# ASM4001.net
KiCad netlist of a schematic drawn in EAGLE
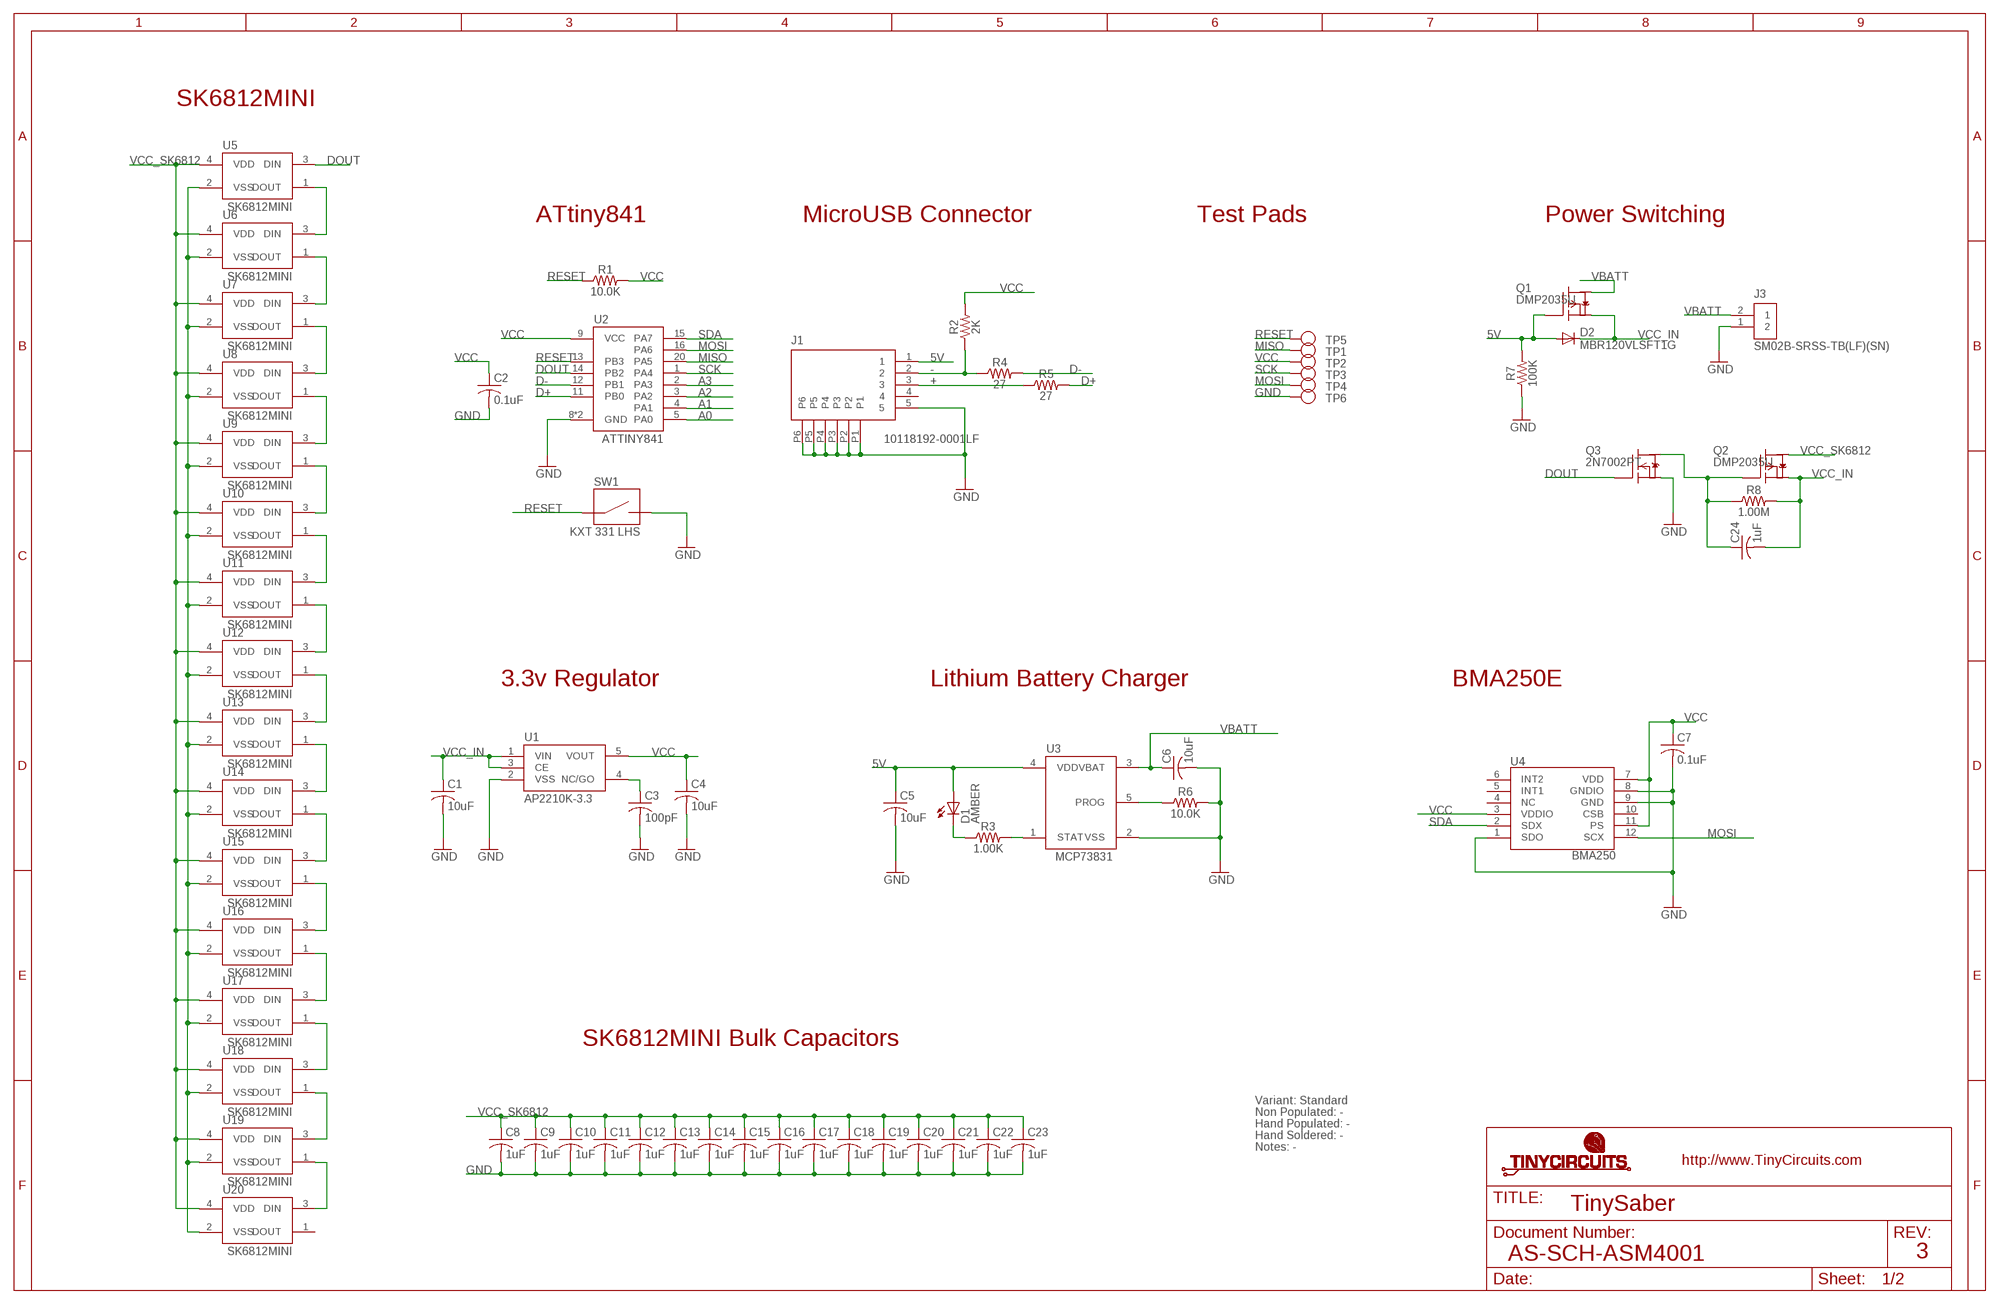
[diagram p0: schematic, sheet 1]

(export (version "E")
  (design (tool "Eeschema 10.0.6"))
  (components
    (comp (ref "C1")
      (value "10uF")
      (footprint "eagle-import:C0603")
      (fields (field (name "PARTNO") "AS-ITM-00002") (field (name "PARTNO_1") "AS-ITM-00002"))
      (libsource (lib "eagle-import") (part "AS-ITM-00002"))
    )
    (comp (ref "C2")
      (value "0.1uF")
      (footprint "eagle-import:C0402")
      (fields (field (name "PARTNO") "AS-ITM-00008"))
      (libsource (lib "eagle-import") (part "AS-ITM-00008"))
    )
    (comp (ref "C3")
      (value "100pF")
      (footprint "eagle-import:0402")
      (fields (field (name "PARTNO") "AS-ITM-00148") (field (name "PARTNO_1") "AS-ITM-00148"))
      (libsource (lib "eagle-import") (part "AS-ITM-00148"))
    )
    (comp (ref "C4")
      (value "10uF")
      (footprint "eagle-import:C0603")
      (fields (field (name "PARTNO") "AS-ITM-00002") (field (name "PARTNO_1") "AS-ITM-00002"))
      (libsource (lib "eagle-import") (part "AS-ITM-00002"))
    )
    (comp (ref "C5")
      (value "10uF")
      (footprint "eagle-import:C0603")
      (fields (field (name "PARTNO") "AS-ITM-00002") (field (name "PARTNO_1") "AS-ITM-00002"))
      (libsource (lib "eagle-import") (part "AS-ITM-00002"))
    )
    (comp (ref "C6")
      (value "10uF")
      (footprint "eagle-import:C0603")
      (fields (field (name "PARTNO") "AS-ITM-00002"))
      (libsource (lib "eagle-import") (part "AS-ITM-00002"))
    )
    (comp (ref "C7")
      (value "0.1uF")
      (footprint "eagle-import:C0402")
      (fields (field (name "PARTNO") "AS-ITM-00008"))
      (libsource (lib "eagle-import") (part "AS-ITM-00008"))
    )
    (comp (ref "C8")
      (value "1uF")
      (footprint "eagle-import:C0603")
      (fields (field (name "PARTNO") "AS-ITM-00410") (field (name "PARTNO_1") "AS-ITM-00410"))
      (libsource (lib "eagle-import") (part "AS-ITM-00410"))
    )
    (comp (ref "C9")
      (value "1uF")
      (footprint "eagle-import:C0603")
      (fields (field (name "PARTNO") "AS-ITM-00410") (field (name "PARTNO_1") "AS-ITM-00410"))
      (libsource (lib "eagle-import") (part "AS-ITM-00410"))
    )
    (comp (ref "C10")
      (value "1uF")
      (footprint "eagle-import:C0603")
      (fields (field (name "PARTNO") "AS-ITM-00410") (field (name "PARTNO_1") "AS-ITM-00410"))
      (libsource (lib "eagle-import") (part "AS-ITM-00410"))
    )
    (comp (ref "C11")
      (value "1uF")
      (footprint "eagle-import:C0603")
      (fields (field (name "PARTNO") "AS-ITM-00410") (field (name "PARTNO_1") "AS-ITM-00410"))
      (libsource (lib "eagle-import") (part "AS-ITM-00410"))
    )
    (comp (ref "C12")
      (value "1uF")
      (footprint "eagle-import:C0603")
      (fields (field (name "PARTNO") "AS-ITM-00410") (field (name "PARTNO_1") "AS-ITM-00410"))
      (libsource (lib "eagle-import") (part "AS-ITM-00410"))
    )
    (comp (ref "C13")
      (value "1uF")
      (footprint "eagle-import:C0603")
      (fields (field (name "PARTNO") "AS-ITM-00410") (field (name "PARTNO_1") "AS-ITM-00410"))
      (libsource (lib "eagle-import") (part "AS-ITM-00410"))
    )
    (comp (ref "C14")
      (value "1uF")
      (footprint "eagle-import:C0603")
      (fields (field (name "PARTNO") "AS-ITM-00410") (field (name "PARTNO_1") "AS-ITM-00410"))
      (libsource (lib "eagle-import") (part "AS-ITM-00410"))
    )
    (comp (ref "C15")
      (value "1uF")
      (footprint "eagle-import:C0603")
      (fields (field (name "PARTNO") "AS-ITM-00410") (field (name "PARTNO_1") "AS-ITM-00410"))
      (libsource (lib "eagle-import") (part "AS-ITM-00410"))
    )
    (comp (ref "C16")
      (value "1uF")
      (footprint "eagle-import:C0603")
      (fields (field (name "PARTNO") "AS-ITM-00410") (field (name "PARTNO_1") "AS-ITM-00410"))
      (libsource (lib "eagle-import") (part "AS-ITM-00410"))
    )
    (comp (ref "C17")
      (value "1uF")
      (footprint "eagle-import:C0603")
      (fields (field (name "PARTNO") "AS-ITM-00410") (field (name "PARTNO_1") "AS-ITM-00410"))
      (libsource (lib "eagle-import") (part "AS-ITM-00410"))
    )
    (comp (ref "C18")
      (value "1uF")
      (footprint "eagle-import:C0603")
      (fields (field (name "PARTNO") "AS-ITM-00410") (field (name "PARTNO_1") "AS-ITM-00410"))
      (libsource (lib "eagle-import") (part "AS-ITM-00410"))
    )
    (comp (ref "C19")
      (value "1uF")
      (footprint "eagle-import:C0603")
      (fields (field (name "PARTNO") "AS-ITM-00410") (field (name "PARTNO_1") "AS-ITM-00410"))
      (libsource (lib "eagle-import") (part "AS-ITM-00410"))
    )
    (comp (ref "C20")
      (value "1uF")
      (footprint "eagle-import:C0603")
      (fields (field (name "PARTNO") "AS-ITM-00410") (field (name "PARTNO_1") "AS-ITM-00410"))
      (libsource (lib "eagle-import") (part "AS-ITM-00410"))
    )
    (comp (ref "C21")
      (value "1uF")
      (footprint "eagle-import:C0603")
      (fields (field (name "PARTNO") "AS-ITM-00410") (field (name "PARTNO_1") "AS-ITM-00410"))
      (libsource (lib "eagle-import") (part "AS-ITM-00410"))
    )
    (comp (ref "C22")
      (value "1uF")
      (footprint "eagle-import:C0603")
      (fields (field (name "PARTNO") "AS-ITM-00410") (field (name "PARTNO_1") "AS-ITM-00410"))
      (libsource (lib "eagle-import") (part "AS-ITM-00410"))
    )
    (comp (ref "C23")
      (value "1uF")
      (footprint "eagle-import:C0603")
      (fields (field (name "PARTNO") "AS-ITM-00410") (field (name "PARTNO_1") "AS-ITM-00410"))
      (libsource (lib "eagle-import") (part "AS-ITM-00410"))
    )
    (comp (ref "C24")
      (value "1uF")
      (footprint "eagle-import:C0402")
      (fields (field (name "PARTNO") "AS-ITM-00105"))
      (libsource (lib "eagle-import") (part "AS-ITM-00105"))
    )
    (comp (ref "D1")
      (value "AMBER")
      (footprint "eagle-import:0402_LED")
      (fields (field (name "PARTNO") "AS-ITM-00058"))
      (libsource (lib "eagle-import") (part "AS-ITM-00058"))
    )
    (comp (ref "D2")
      (value "MBR120VLSFT1G")
      (footprint "eagle-import:SOD-123FL")
      (fields (field (name "PARTNO") "AS-ITM-00111") (field (name "PARTNO_1") "AS-ITM-00111"))
      (libsource (lib "eagle-import") (part "AS-ITM-00111"))
    )
    (comp (ref "J1")
      (value "10118192-0001LF")
      (footprint "eagle-import:MICRO_USB_ALT")
      (fields (field (name "PARTNO") "AS-ITM-00021"))
      (libsource (lib "eagle-import") (part "AS-ITM-00021A"))
    )
    (comp (ref "J3")
      (value "SM02B-SRSS-TB(LF)(SN)")
      (footprint "eagle-import:JST_SH_2X1")
      (fields (field (name "PARTNO") "AS-ITM-00231"))
      (libsource (lib "eagle-import") (part "AS-ITM-00231"))
    )
    (comp (ref "Q1")
      (value "DMP2035U")
      (footprint "eagle-import:SOT23")
      (fields (field (name "PARTNO") "AS-ITM-00024"))
      (libsource (lib "eagle-import") (part "AS-ITM-00024"))
    )
    (comp (ref "Q2")
      (value "DMP2035U")
      (footprint "eagle-import:SOT23A")
      (fields (field (name "PARTNO") "AS-ITM-0024") (field (name "PARTNO_1") "AS-ITM-00024"))
      (libsource (lib "eagle-import") (part "AS-ITM-00024A"))
    )
    (comp (ref "Q3")
      (value "2N7002PT")
      (footprint "eagle-import:SOT-416")
      (fields (field (name "PARTNO") "AS-ITM-00110"))
      (libsource (lib "eagle-import") (part "AS-ITM-00110"))
    )
    (comp (ref "R1")
      (value "10.0K")
      (footprint "eagle-import:0402")
      (fields (field (name "PARTNO") "AS-ITM-00032"))
      (libsource (lib "eagle-import") (part "AS-ITM-00032"))
    )
    (comp (ref "R2")
      (value "2K")
      (footprint "eagle-import:0402")
      (fields (field (name "PARTNO") "AS-ITM-00315"))
      (libsource (lib "eagle-import") (part "AS-ITM-00315"))
    )
    (comp (ref "R3")
      (value "1.00K")
      (footprint "eagle-import:0402")
      (fields (field (name "PARTNO") "AS-ITM-00003"))
      (libsource (lib "eagle-import") (part "AS-ITM-00003"))
    )
    (comp (ref "R4")
      (value "27")
      (footprint "eagle-import:0402")
      (fields (field (name "PARTNO") "AS-ITM-00240") (field (name "PARTNO_1") "AS-ITM-00240"))
      (libsource (lib "eagle-import") (part "AS-ITM-00240"))
    )
    (comp (ref "R5")
      (value "27")
      (footprint "eagle-import:0402")
      (fields (field (name "PARTNO") "AS-ITM-00240") (field (name "PARTNO_1") "AS-ITM-00240"))
      (libsource (lib "eagle-import") (part "AS-ITM-00240"))
    )
    (comp (ref "R6")
      (value "10.0K")
      (footprint "eagle-import:0402")
      (fields (field (name "PARTNO") "AS-ITM-00032"))
      (libsource (lib "eagle-import") (part "AS-ITM-00032"))
    )
    (comp (ref "R7")
      (value "100K")
      (footprint "eagle-import:0402")
      (fields (field (name "PARTNO") "AS-ITM-00004"))
      (libsource (lib "eagle-import") (part "AS-ITM-00004"))
    )
    (comp (ref "R8")
      (value "1.00M")
      (footprint "eagle-import:0402")
      (fields (field (name "PARTNO") "AS-ITM-00005") (field (name "PARTNO_1") "AS-ITM-00005"))
      (libsource (lib "eagle-import") (part "AS-ITM-00005"))
    )
    (comp (ref "SW1")
      (value "KXT 331 LHS")
      (footprint "eagle-import:KXT_LHS")
      (fields (field (name "PARTNO") "AS-ITM-00372"))
      (libsource (lib "eagle-import") (part "AS-ITM-00372"))
    )
    (comp (ref "TP1")
      (value "TEST_POINT")
      (footprint "eagle-import:TEST_POINT_1MM")
      (libsource (lib "eagle-import") (part "TEST_POINT"))
    )
    (comp (ref "TP2")
      (value "TEST_POINT")
      (footprint "eagle-import:TEST_POINT_1MM")
      (libsource (lib "eagle-import") (part "TEST_POINT"))
    )
    (comp (ref "TP3")
      (value "TEST_POINT")
      (footprint "eagle-import:TEST_POINT_1MM")
      (libsource (lib "eagle-import") (part "TEST_POINT"))
    )
    (comp (ref "TP4")
      (value "TEST_POINT")
      (footprint "eagle-import:TEST_POINT_1MM")
      (libsource (lib "eagle-import") (part "TEST_POINT"))
    )
    (comp (ref "TP5")
      (value "TEST_POINT")
      (footprint "eagle-import:TEST_POINT_1MM")
      (libsource (lib "eagle-import") (part "TEST_POINT"))
    )
    (comp (ref "TP6")
      (value "TEST_POINT")
      (footprint "eagle-import:TEST_POINT_1MM")
      (libsource (lib "eagle-import") (part "TEST_POINT"))
    )
    (comp (ref "U1")
      (value "AP2210K-3.3")
      (footprint "eagle-import:SOT-25")
      (fields (field (name "PARTNO") "AS-ITM-00344") (field (name "PARTNO_1") "AS-ITM-00344"))
      (libsource (lib "eagle-import") (part "AS-ITM-00344"))
    )
    (comp (ref "U2")
      (value "ATTINY841")
      (footprint "eagle-import:VQFN-20")
      (fields (field (name "PARTNO") "AS-ITM-00255"))
      (libsource (lib "eagle-import") (part "AS-ITM-00255"))
    )
    (comp (ref "U3")
      (value "MCP73831")
      (footprint "eagle-import:SOT-23")
      (fields (field (name "PARTNO") "AS-ITM-00136"))
      (libsource (lib "eagle-import") (part "AS-ITM-00136"))
    )
    (comp (ref "U4")
      (value "BMA250")
      (footprint "eagle-import:3-AXIS_ACCELEROMETER")
      (fields (field (name "PARTNO") "AS-ITM-00070"))
      (libsource (lib "eagle-import") (part "AS-ITM-00070"))
    )
    (comp (ref "U5")
      (value "SK6812MINI")
      (footprint "eagle-import:SK6812MINI")
      (fields (field (name "PARTNO") "AS-ITM-00343") (field (name "PARTNO_1") "AS-ITM-00343"))
      (libsource (lib "eagle-import") (part "AS-ITM-00343"))
    )
    (comp (ref "U6")
      (value "SK6812MINI")
      (footprint "eagle-import:SK6812MINI")
      (fields (field (name "PARTNO") "AS-ITM-00343") (field (name "PARTNO_1") "AS-ITM-00343"))
      (libsource (lib "eagle-import") (part "AS-ITM-00343"))
    )
    (comp (ref "U7")
      (value "SK6812MINI")
      (footprint "eagle-import:SK6812MINI")
      (fields (field (name "PARTNO") "AS-ITM-00343") (field (name "PARTNO_1") "AS-ITM-00343"))
      (libsource (lib "eagle-import") (part "AS-ITM-00343"))
    )
    (comp (ref "U8")
      (value "SK6812MINI")
      (footprint "eagle-import:SK6812MINI")
      (fields (field (name "PARTNO") "AS-ITM-00343") (field (name "PARTNO_1") "AS-ITM-00343"))
      (libsource (lib "eagle-import") (part "AS-ITM-00343"))
    )
    (comp (ref "U9")
      (value "SK6812MINI")
      (footprint "eagle-import:SK6812MINI")
      (fields (field (name "PARTNO") "AS-ITM-00343") (field (name "PARTNO_1") "AS-ITM-00343"))
      (libsource (lib "eagle-import") (part "AS-ITM-00343"))
    )
    (comp (ref "U10")
      (value "SK6812MINI")
      (footprint "eagle-import:SK6812MINI")
      (fields (field (name "PARTNO") "AS-ITM-00343") (field (name "PARTNO_1") "AS-ITM-00343"))
      (libsource (lib "eagle-import") (part "AS-ITM-00343"))
    )
    (comp (ref "U11")
      (value "SK6812MINI")
      (footprint "eagle-import:SK6812MINI")
      (fields (field (name "PARTNO") "AS-ITM-00343") (field (name "PARTNO_1") "AS-ITM-00343"))
      (libsource (lib "eagle-import") (part "AS-ITM-00343"))
    )
    (comp (ref "U12")
      (value "SK6812MINI")
      (footprint "eagle-import:SK6812MINI")
      (fields (field (name "PARTNO") "AS-ITM-00343") (field (name "PARTNO_1") "AS-ITM-00343"))
      (libsource (lib "eagle-import") (part "AS-ITM-00343"))
    )
    (comp (ref "U13")
      (value "SK6812MINI")
      (footprint "eagle-import:SK6812MINI")
      (fields (field (name "PARTNO") "AS-ITM-00343") (field (name "PARTNO_1") "AS-ITM-00343"))
      (libsource (lib "eagle-import") (part "AS-ITM-00343"))
    )
    (comp (ref "U14")
      (value "SK6812MINI")
      (footprint "eagle-import:SK6812MINI")
      (fields (field (name "PARTNO") "AS-ITM-00343") (field (name "PARTNO_1") "AS-ITM-00343"))
      (libsource (lib "eagle-import") (part "AS-ITM-00343"))
    )
    (comp (ref "U15")
      (value "SK6812MINI")
      (footprint "eagle-import:SK6812MINI")
      (fields (field (name "PARTNO") "AS-ITM-00343") (field (name "PARTNO_1") "AS-ITM-00343"))
      (libsource (lib "eagle-import") (part "AS-ITM-00343"))
    )
    (comp (ref "U16")
      (value "SK6812MINI")
      (footprint "eagle-import:SK6812MINI")
      (fields (field (name "PARTNO") "AS-ITM-00343") (field (name "PARTNO_1") "AS-ITM-00343"))
      (libsource (lib "eagle-import") (part "AS-ITM-00343"))
    )
    (comp (ref "U17")
      (value "SK6812MINI")
      (footprint "eagle-import:SK6812MINI")
      (fields (field (name "PARTNO") "AS-ITM-00343") (field (name "PARTNO_1") "AS-ITM-00343"))
      (libsource (lib "eagle-import") (part "AS-ITM-00343"))
    )
    (comp (ref "U18")
      (value "SK6812MINI")
      (footprint "eagle-import:SK6812MINI")
      (fields (field (name "PARTNO") "AS-ITM-00343") (field (name "PARTNO_1") "AS-ITM-00343"))
      (libsource (lib "eagle-import") (part "AS-ITM-00343"))
    )
    (comp (ref "U19")
      (value "SK6812MINI")
      (footprint "eagle-import:SK6812MINI")
      (fields (field (name "PARTNO") "AS-ITM-00343") (field (name "PARTNO_1") "AS-ITM-00343"))
      (libsource (lib "eagle-import") (part "AS-ITM-00343"))
    )
    (comp (ref "U20")
      (value "SK6812MINI")
      (footprint "eagle-import:SK6812MINI")
      (fields (field (name "PARTNO") "AS-ITM-00343") (field (name "PARTNO_1") "AS-ITM-00343"))
      (libsource (lib "eagle-import") (part "AS-ITM-00343"))
    )
  )
  (nets
    (net (code "1") (name "+") (class "Default")
      (node (ref "J1") (pin "3") (pinfunction "3_3") (pintype "bidirectional"))
      (node (ref "R5") (pin "1") (pinfunction "1_1") (pintype "passive"))
    )
    (net (code "2") (name "-") (class "Default")
      (node (ref "J1") (pin "2") (pinfunction "2_2") (pintype "bidirectional"))
      (node (ref "R2") (pin "1") (pinfunction "1_1") (pintype "passive"))
      (node (ref "R4") (pin "1") (pinfunction "1_1") (pintype "passive"))
    )
    (net (code "3") (name "5V") (class "Default")
      (node (ref "C5") (pin "1") (pinfunction "1_1") (pintype "passive"))
      (node (ref "D1") (pin "1") (pinfunction "A_1") (pintype "passive"))
      (node (ref "D2") (pin "A") (pinfunction "A_A") (pintype "passive"))
      (node (ref "J1") (pin "1") (pinfunction "1_1") (pintype "bidirectional"))
      (node (ref "Q1") (pin "B") (pinfunction "G_B") (pintype "passive"))
      (node (ref "R7") (pin "2") (pinfunction "2_2") (pintype "passive"))
      (node (ref "U3") (pin "4") (pinfunction "VDD_4") (pintype "bidirectional"))
    )
    (net (code "4") (name "A0") (class "Default")
      (node (ref "U2") (pin "5") (pinfunction "PA0_5") (pintype "bidirectional"))
    )
    (net (code "5") (name "A1") (class "Default")
      (node (ref "U2") (pin "4") (pinfunction "PA1_4") (pintype "bidirectional"))
    )
    (net (code "6") (name "A2") (class "Default")
      (node (ref "U2") (pin "3") (pinfunction "PA2_3") (pintype "bidirectional"))
    )
    (net (code "7") (name "A3") (class "Default")
      (node (ref "U2") (pin "2") (pinfunction "PA3_2") (pintype "bidirectional"))
    )
    (net (code "8") (name "D+") (class "Default")
      (node (ref "R5") (pin "2") (pinfunction "2_2") (pintype "passive"))
      (node (ref "U2") (pin "11") (pinfunction "PB0_11") (pintype "bidirectional"))
    )
    (net (code "9") (name "D-") (class "Default")
      (node (ref "R4") (pin "2") (pinfunction "2_2") (pintype "passive"))
      (node (ref "U2") (pin "12") (pinfunction "PB1_12") (pintype "bidirectional"))
    )
    (net (code "10") (name "DOUT") (class "Default")
      (node (ref "Q3") (pin "1") (pinfunction "G_1") (pintype "passive"))
      (node (ref "U2") (pin "14") (pinfunction "PB2_14") (pintype "bidirectional"))
      (node (ref "U5") (pin "3") (pinfunction "DIN_3") (pintype "bidirectional"))
    )
    (net (code "11") (name "GND") (class "Default")
      (node (ref "C1") (pin "2") (pinfunction "2_2") (pintype "passive"))
      (node (ref "C10") (pin "2") (pinfunction "2_2") (pintype "passive"))
      (node (ref "C11") (pin "2") (pinfunction "2_2") (pintype "passive"))
      (node (ref "C12") (pin "2") (pinfunction "2_2") (pintype "passive"))
      (node (ref "C13") (pin "2") (pinfunction "2_2") (pintype "passive"))
      (node (ref "C14") (pin "2") (pinfunction "2_2") (pintype "passive"))
      (node (ref "C15") (pin "2") (pinfunction "2_2") (pintype "passive"))
      (node (ref "C16") (pin "2") (pinfunction "2_2") (pintype "passive"))
      (node (ref "C17") (pin "2") (pinfunction "2_2") (pintype "passive"))
      (node (ref "C18") (pin "2") (pinfunction "2_2") (pintype "passive"))
      (node (ref "C19") (pin "2") (pinfunction "2_2") (pintype "passive"))
      (node (ref "C2") (pin "2") (pinfunction "2_2") (pintype "passive"))
      (node (ref "C20") (pin "2") (pinfunction "2_2") (pintype "passive"))
      (node (ref "C21") (pin "2") (pinfunction "2_2") (pintype "passive"))
      (node (ref "C22") (pin "2") (pinfunction "2_2") (pintype "passive"))
      (node (ref "C23") (pin "2") (pinfunction "2_2") (pintype "passive"))
      (node (ref "C3") (pin "2") (pinfunction "2_2") (pintype "passive"))
      (node (ref "C4") (pin "2") (pinfunction "2_2") (pintype "passive"))
      (node (ref "C5") (pin "2") (pinfunction "2_2") (pintype "passive"))
      (node (ref "C6") (pin "2") (pinfunction "2_2") (pintype "passive"))
      (node (ref "C7") (pin "2") (pinfunction "2_2") (pintype "passive"))
      (node (ref "C8") (pin "2") (pinfunction "2_2") (pintype "passive"))
      (node (ref "C9") (pin "2") (pinfunction "2_2") (pintype "passive"))
      (node (ref "J1") (pin "5") (pinfunction "5_5") (pintype "bidirectional"))
      (node (ref "J1") (pin "P1") (pinfunction "P1_P1") (pintype "bidirectional"))
      (node (ref "J1") (pin "P2") (pinfunction "P2_P2") (pintype "bidirectional"))
      (node (ref "J1") (pin "P3") (pinfunction "P3_P3") (pintype "bidirectional"))
      (node (ref "J1") (pin "P4") (pinfunction "P4_P4") (pintype "bidirectional"))
      (node (ref "J1") (pin "P5") (pinfunction "P5_P5") (pintype "bidirectional"))
      (node (ref "J1") (pin "P6") (pinfunction "P6_P6") (pintype "bidirectional"))
      (node (ref "J3") (pin "1") (pinfunction "2_1") (pintype "bidirectional"))
      (node (ref "Q3") (pin "2") (pinfunction "S_2") (pintype "passive"))
      (node (ref "R6") (pin "2") (pinfunction "2_2") (pintype "passive"))
      (node (ref "R7") (pin "1") (pinfunction "1_1") (pintype "passive"))
      (node (ref "SW1") (pin "2") (pinfunction "2_2") (pintype "bidirectional"))
      (node (ref "TP6") (pin "P$1") (pinfunction "1_P$1") (pintype "bidirectional"))
      (node (ref "U1") (pin "2") (pinfunction "VSS_2") (pintype "power_in"))
      (node (ref "U10") (pin "2") (pinfunction "VSS_2") (pintype "bidirectional"))
      (node (ref "U11") (pin "2") (pinfunction "VSS_2") (pintype "bidirectional"))
      (node (ref "U12") (pin "2") (pinfunction "VSS_2") (pintype "bidirectional"))
      (node (ref "U13") (pin "2") (pinfunction "VSS_2") (pintype "bidirectional"))
      (node (ref "U14") (pin "2") (pinfunction "VSS_2") (pintype "bidirectional"))
      (node (ref "U15") (pin "2") (pinfunction "VSS_2") (pintype "bidirectional"))
      (node (ref "U16") (pin "2") (pinfunction "VSS_2") (pintype "bidirectional"))
      (node (ref "U17") (pin "2") (pinfunction "VSS_2") (pintype "bidirectional"))
      (node (ref "U18") (pin "2") (pinfunction "VSS_2") (pintype "bidirectional"))
      (node (ref "U19") (pin "2") (pinfunction "VSS_2") (pintype "bidirectional"))
      (node (ref "U2") (pin "8") (pinfunction "GND_8") (pintype "bidirectional"))
      (node (ref "U2") (pin "PAD") (pinfunction "GND_PAD") (pintype "bidirectional"))
      (node (ref "U20") (pin "2") (pinfunction "VSS_2") (pintype "bidirectional"))
      (node (ref "U3") (pin "2") (pinfunction "VSS_2") (pintype "bidirectional"))
      (node (ref "U4") (pin "1") (pinfunction "SDO_1") (pintype "bidirectional"))
      (node (ref "U4") (pin "8") (pinfunction "GNDIO_8") (pintype "bidirectional"))
      (node (ref "U4") (pin "9") (pinfunction "GND_9") (pintype "bidirectional"))
      (node (ref "U5") (pin "2") (pinfunction "VSS_2") (pintype "bidirectional"))
      (node (ref "U6") (pin "2") (pinfunction "VSS_2") (pintype "bidirectional"))
      (node (ref "U7") (pin "2") (pinfunction "VSS_2") (pintype "bidirectional"))
      (node (ref "U8") (pin "2") (pinfunction "VSS_2") (pintype "bidirectional"))
      (node (ref "U9") (pin "2") (pinfunction "VSS_2") (pintype "bidirectional"))
    )
    (net (code "12") (name "MISO") (class "Default")
      (node (ref "TP1") (pin "P$1") (pinfunction "1_P$1") (pintype "bidirectional"))
      (node (ref "U2") (pin "20") (pinfunction "PA5_20") (pintype "bidirectional"))
    )
    (net (code "13") (name "MOSI") (class "Default")
      (node (ref "TP4") (pin "P$1") (pinfunction "1_P$1") (pintype "bidirectional"))
      (node (ref "U2") (pin "16") (pinfunction "PA6_16") (pintype "bidirectional"))
      (node (ref "U4") (pin "12") (pinfunction "SCX_12") (pintype "bidirectional"))
    )
    (net (code "14") (name "Net-(D1-C)") (class "Default")
      (node (ref "D1") (pin "2") (pinfunction "C_2") (pintype "passive"))
      (node (ref "R3") (pin "1") (pinfunction "1_1") (pintype "passive"))
    )
    (net (code "15") (name "Net-(Q2-G)") (class "Default")
      (node (ref "C24") (pin "1") (pinfunction "1_1") (pintype "passive"))
      (node (ref "Q2") (pin "B") (pinfunction "G_B") (pintype "passive"))
      (node (ref "Q3") (pin "3") (pinfunction "D_3") (pintype "passive"))
      (node (ref "R8") (pin "1") (pinfunction "1_1") (pintype "passive"))
    )
    (net (code "16") (name "Net-(U1-NC{slash}GO)") (class "Default")
      (node (ref "C3") (pin "1") (pinfunction "1_1") (pintype "passive"))
      (node (ref "U1") (pin "4") (pinfunction "NC/GO_4") (pintype "bidirectional"))
    )
    (net (code "17") (name "Net-(U3-PROG)") (class "Default")
      (node (ref "R6") (pin "1") (pinfunction "1_1") (pintype "passive"))
      (node (ref "U3") (pin "5") (pinfunction "PROG_5") (pintype "bidirectional"))
    )
    (net (code "18") (name "Net-(U3-STAT)") (class "Default")
      (node (ref "R3") (pin "2") (pinfunction "2_2") (pintype "passive"))
      (node (ref "U3") (pin "1") (pinfunction "STAT_1") (pintype "bidirectional"))
    )
    (net (code "19") (name "Net-(U5-DOUT)") (class "Default")
      (node (ref "U5") (pin "1") (pinfunction "DOUT_1") (pintype "bidirectional"))
      (node (ref "U6") (pin "3") (pinfunction "DIN_3") (pintype "bidirectional"))
    )
    (net (code "20") (name "Net-(U6-DOUT)") (class "Default")
      (node (ref "U6") (pin "1") (pinfunction "DOUT_1") (pintype "bidirectional"))
      (node (ref "U7") (pin "3") (pinfunction "DIN_3") (pintype "bidirectional"))
    )
    (net (code "21") (name "Net-(U7-DOUT)") (class "Default")
      (node (ref "U7") (pin "1") (pinfunction "DOUT_1") (pintype "bidirectional"))
      (node (ref "U8") (pin "3") (pinfunction "DIN_3") (pintype "bidirectional"))
    )
    (net (code "22") (name "Net-(U8-DOUT)") (class "Default")
      (node (ref "U8") (pin "1") (pinfunction "DOUT_1") (pintype "bidirectional"))
      (node (ref "U9") (pin "3") (pinfunction "DIN_3") (pintype "bidirectional"))
    )
    (net (code "23") (name "Net-(U10-DIN)") (class "Default")
      (node (ref "U10") (pin "3") (pinfunction "DIN_3") (pintype "bidirectional"))
      (node (ref "U9") (pin "1") (pinfunction "DOUT_1") (pintype "bidirectional"))
    )
    (net (code "24") (name "Net-(U10-DOUT)") (class "Default")
      (node (ref "U10") (pin "1") (pinfunction "DOUT_1") (pintype "bidirectional"))
      (node (ref "U11") (pin "3") (pinfunction "DIN_3") (pintype "bidirectional"))
    )
    (net (code "25") (name "Net-(U11-DOUT)") (class "Default")
      (node (ref "U11") (pin "1") (pinfunction "DOUT_1") (pintype "bidirectional"))
      (node (ref "U12") (pin "3") (pinfunction "DIN_3") (pintype "bidirectional"))
    )
    (net (code "26") (name "Net-(U12-DOUT)") (class "Default")
      (node (ref "U12") (pin "1") (pinfunction "DOUT_1") (pintype "bidirectional"))
      (node (ref "U13") (pin "3") (pinfunction "DIN_3") (pintype "bidirectional"))
    )
    (net (code "27") (name "Net-(U13-DOUT)") (class "Default")
      (node (ref "U13") (pin "1") (pinfunction "DOUT_1") (pintype "bidirectional"))
      (node (ref "U14") (pin "3") (pinfunction "DIN_3") (pintype "bidirectional"))
    )
    (net (code "28") (name "Net-(U14-DOUT)") (class "Default")
      (node (ref "U14") (pin "1") (pinfunction "DOUT_1") (pintype "bidirectional"))
      (node (ref "U15") (pin "3") (pinfunction "DIN_3") (pintype "bidirectional"))
    )
    (net (code "29") (name "Net-(U15-DOUT)") (class "Default")
      (node (ref "U15") (pin "1") (pinfunction "DOUT_1") (pintype "bidirectional"))
      (node (ref "U16") (pin "3") (pinfunction "DIN_3") (pintype "bidirectional"))
    )
    (net (code "30") (name "Net-(U16-DOUT)") (class "Default")
      (node (ref "U16") (pin "1") (pinfunction "DOUT_1") (pintype "bidirectional"))
      (node (ref "U17") (pin "3") (pinfunction "DIN_3") (pintype "bidirectional"))
    )
    (net (code "31") (name "Net-(U17-DOUT)") (class "Default")
      (node (ref "U17") (pin "1") (pinfunction "DOUT_1") (pintype "bidirectional"))
      (node (ref "U18") (pin "3") (pinfunction "DIN_3") (pintype "bidirectional"))
    )
    (net (code "32") (name "Net-(U18-DOUT)") (class "Default")
      (node (ref "U18") (pin "1") (pinfunction "DOUT_1") (pintype "bidirectional"))
      (node (ref "U19") (pin "3") (pinfunction "DIN_3") (pintype "bidirectional"))
    )
    (net (code "33") (name "Net-(U19-DOUT)") (class "Default")
      (node (ref "U19") (pin "1") (pinfunction "DOUT_1") (pintype "bidirectional"))
      (node (ref "U20") (pin "3") (pinfunction "DIN_3") (pintype "bidirectional"))
    )
    (net (code "34") (name "RESET") (class "Default")
      (node (ref "R1") (pin "1") (pinfunction "1_1") (pintype "passive"))
      (node (ref "SW1") (pin "1") (pinfunction "1_1") (pintype "bidirectional"))
      (node (ref "TP5") (pin "P$1") (pinfunction "1_P$1") (pintype "bidirectional"))
      (node (ref "U2") (pin "13") (pinfunction "PB3_13") (pintype "bidirectional"))
    )
    (net (code "35") (name "SCK") (class "Default")
      (node (ref "TP3") (pin "P$1") (pinfunction "1_P$1") (pintype "bidirectional"))
      (node (ref "U2") (pin "1") (pinfunction "PA4_1") (pintype "bidirectional"))
    )
    (net (code "36") (name "SDA") (class "Default")
      (node (ref "U2") (pin "15") (pinfunction "PA7_15") (pintype "bidirectional"))
      (node (ref "U4") (pin "2") (pinfunction "SDX_2") (pintype "bidirectional"))
    )
    (net (code "37") (name "VBATT") (class "Default")
      (node (ref "C6") (pin "1") (pinfunction "1_1") (pintype "passive"))
      (node (ref "J3") (pin "2") (pinfunction "1_2") (pintype "bidirectional"))
      (node (ref "Q1") (pin "C") (pinfunction "D_C") (pintype "passive"))
      (node (ref "U3") (pin "3") (pinfunction "VBAT_3") (pintype "bidirectional"))
    )
    (net (code "38") (name "VCC") (class "Default")
      (node (ref "C2") (pin "1") (pinfunction "1_1") (pintype "passive"))
      (node (ref "C4") (pin "1") (pinfunction "1_1") (pintype "passive"))
      (node (ref "C7") (pin "1") (pinfunction "1_1") (pintype "passive"))
      (node (ref "R1") (pin "2") (pinfunction "2_2") (pintype "passive"))
      (node (ref "R2") (pin "2") (pinfunction "2_2") (pintype "passive"))
      (node (ref "TP2") (pin "P$1") (pinfunction "1_P$1") (pintype "bidirectional"))
      (node (ref "U1") (pin "5") (pinfunction "VOUT_5") (pintype "bidirectional"))
      (node (ref "U2") (pin "9") (pinfunction "VCC_9") (pintype "bidirectional"))
      (node (ref "U4") (pin "11") (pinfunction "PS_11") (pintype "bidirectional"))
      (node (ref "U4") (pin "3") (pinfunction "VDDIO_3") (pintype "bidirectional"))
      (node (ref "U4") (pin "7") (pinfunction "VDD_7") (pintype "bidirectional"))
    )
    (net (code "39") (name "VCC_IN") (class "Default")
      (node (ref "C1") (pin "1") (pinfunction "1_1") (pintype "passive"))
      (node (ref "C24") (pin "2") (pinfunction "2_2") (pintype "passive"))
      (node (ref "D2") (pin "C") (pinfunction "C_C") (pintype "passive"))
      (node (ref "Q1") (pin "E") (pinfunction "S_E") (pintype "passive"))
      (node (ref "Q2") (pin "E") (pinfunction "S_E") (pintype "passive"))
      (node (ref "R8") (pin "2") (pinfunction "2_2") (pintype "passive"))
      (node (ref "U1") (pin "1") (pinfunction "VIN_1") (pintype "bidirectional"))
      (node (ref "U1") (pin "3") (pinfunction "CE_3") (pintype "bidirectional"))
    )
    (net (code "40") (name "VCC_SK6812") (class "Default")
      (node (ref "C10") (pin "1") (pinfunction "1_1") (pintype "passive"))
      (node (ref "C11") (pin "1") (pinfunction "1_1") (pintype "passive"))
      (node (ref "C12") (pin "1") (pinfunction "1_1") (pintype "passive"))
      (node (ref "C13") (pin "1") (pinfunction "1_1") (pintype "passive"))
      (node (ref "C14") (pin "1") (pinfunction "1_1") (pintype "passive"))
      (node (ref "C15") (pin "1") (pinfunction "1_1") (pintype "passive"))
      (node (ref "C16") (pin "1") (pinfunction "1_1") (pintype "passive"))
      (node (ref "C17") (pin "1") (pinfunction "1_1") (pintype "passive"))
      (node (ref "C18") (pin "1") (pinfunction "1_1") (pintype "passive"))
      (node (ref "C19") (pin "1") (pinfunction "1_1") (pintype "passive"))
      (node (ref "C20") (pin "1") (pinfunction "1_1") (pintype "passive"))
      (node (ref "C21") (pin "1") (pinfunction "1_1") (pintype "passive"))
      (node (ref "C22") (pin "1") (pinfunction "1_1") (pintype "passive"))
      (node (ref "C23") (pin "1") (pinfunction "1_1") (pintype "passive"))
      (node (ref "C8") (pin "1") (pinfunction "1_1") (pintype "passive"))
      (node (ref "C9") (pin "1") (pinfunction "1_1") (pintype "passive"))
      (node (ref "Q2") (pin "C") (pinfunction "D_C") (pintype "passive"))
      (node (ref "U10") (pin "4") (pinfunction "VDD_4") (pintype "bidirectional"))
      (node (ref "U11") (pin "4") (pinfunction "VDD_4") (pintype "bidirectional"))
      (node (ref "U12") (pin "4") (pinfunction "VDD_4") (pintype "bidirectional"))
      (node (ref "U13") (pin "4") (pinfunction "VDD_4") (pintype "bidirectional"))
      (node (ref "U14") (pin "4") (pinfunction "VDD_4") (pintype "bidirectional"))
      (node (ref "U15") (pin "4") (pinfunction "VDD_4") (pintype "bidirectional"))
      (node (ref "U16") (pin "4") (pinfunction "VDD_4") (pintype "bidirectional"))
      (node (ref "U17") (pin "4") (pinfunction "VDD_4") (pintype "bidirectional"))
      (node (ref "U18") (pin "4") (pinfunction "VDD_4") (pintype "bidirectional"))
      (node (ref "U19") (pin "4") (pinfunction "VDD_4") (pintype "bidirectional"))
      (node (ref "U20") (pin "4") (pinfunction "VDD_4") (pintype "bidirectional"))
      (node (ref "U5") (pin "4") (pinfunction "VDD_4") (pintype "bidirectional"))
      (node (ref "U6") (pin "4") (pinfunction "VDD_4") (pintype "bidirectional"))
      (node (ref "U7") (pin "4") (pinfunction "VDD_4") (pintype "bidirectional"))
      (node (ref "U8") (pin "4") (pinfunction "VDD_4") (pintype "bidirectional"))
      (node (ref "U9") (pin "4") (pinfunction "VDD_4") (pintype "bidirectional"))
    )
    (net (code "41") (name "unconnected-(J1-Pad4)") (class "Default")
      (node (ref "J1") (pin "4") (pinfunction "4_4") (pintype "bidirectional"))
    )
    (net (code "42") (name "unconnected-(U4-CSB-Pad10)") (class "Default")
      (node (ref "U4") (pin "10") (pinfunction "CSB_10") (pintype "bidirectional"))
    )
    (net (code "43") (name "unconnected-(U4-INT1-Pad5)") (class "Default")
      (node (ref "U4") (pin "5") (pinfunction "INT1_5") (pintype "bidirectional"))
    )
    (net (code "44") (name "unconnected-(U4-INT2-Pad6)") (class "Default")
      (node (ref "U4") (pin "6") (pinfunction "INT2_6") (pintype "bidirectional"))
    )
    (net (code "45") (name "unconnected-(U4-NC-Pad4)") (class "Default")
      (node (ref "U4") (pin "4") (pinfunction "NC_4") (pintype "bidirectional"))
    )
    (net (code "46") (name "unconnected-(U20-DOUT-Pad1)") (class "Default")
      (node (ref "U20") (pin "1") (pinfunction "DOUT_1") (pintype "bidirectional"))
    )
  )
)
